# DUBEC.net
KiCad netlist of a schematic drawn in EAGLE
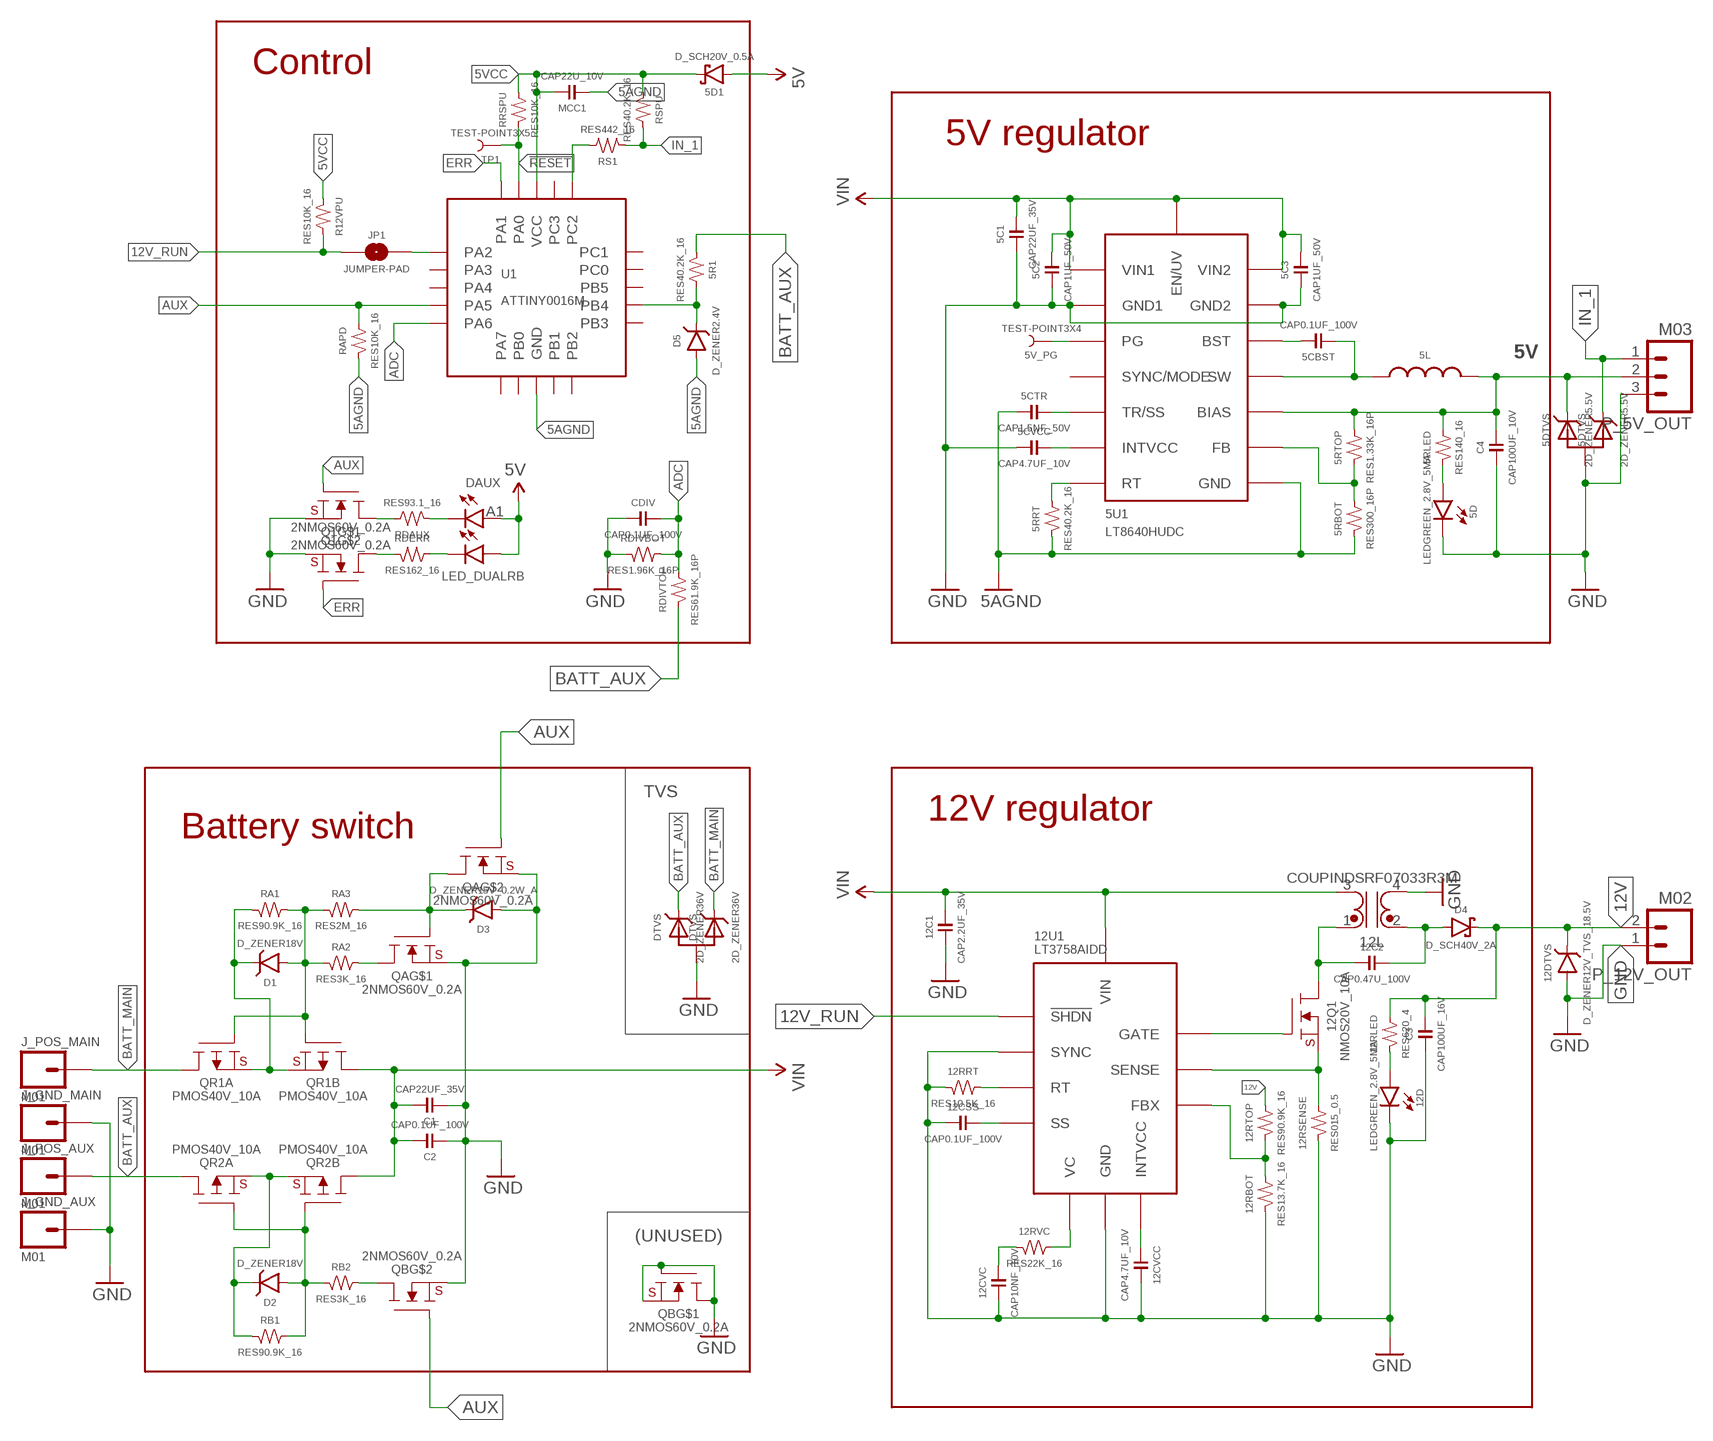
[diagram p0: schematic, sheet 1]

(export (version "E")
  (design (tool "Eeschema 10.0.6"))
  (components
    (comp (ref "5C1")
      (value "CAP22UF_35V")
      (footprint "eagle-import:0805")
      (fields
        (field (name "DIGIKEY_PART_#") "445-14428-1-ND")
        (field (name "MANUFACTURER") "TDK Corporation")
        (field (name "MFG_PART_#") "C2012X5R1V226M125AC")
      )
      (libsource (lib "eagle-import") (part "CAP22UF_35V"))
    )
    (comp (ref "5C2")
      (value "CAP1UF_50V")
      (footprint "eagle-import:0603")
      (fields
        (field (name "DIGIKEY_PART_#") "587-3247-1-ND")
        (field (name "MANUFACTURER") "Taiyo Yuden")
        (field (name "MFG_PART_#") "UMK107AB7105KA-T")
      )
      (libsource (lib "eagle-import") (part "CAP1UF_50V"))
    )
    (comp (ref "5C3")
      (value "CAP1UF_50V")
      (footprint "eagle-import:0603")
      (fields
        (field (name "DIGIKEY_PART_#") "587-3247-1-ND")
        (field (name "MANUFACTURER") "Taiyo Yuden")
        (field (name "MFG_PART_#") "UMK107AB7105KA-T")
      )
      (libsource (lib "eagle-import") (part "CAP1UF_50V"))
    )
    (comp (ref "5CBST")
      (value "CAP0.1UF_100V")
      (footprint "eagle-import:0402")
      (fields
        (field (name "DIGIKEY_PART_#") "490-10458-1-ND")
        (field (name "MANUFACTURER") "Murata Electronics North America")
        (field (name "MFG_PART_#") "GRM155R62A104KE14D")
      )
      (libsource (lib "eagle-import") (part "CAP0.1UF_100V"))
    )
    (comp (ref "5CTR")
      (value "CAP1.5NF_50V")
      (footprint "eagle-import:0402")
      (fields
        (field (name "DIGIKEY_PART_#") "490-3245-1-ND")
        (field (name "MANUFACTURER") "Murata Electronics North America")
        (field (name "MFG_PART_#") "GRM155R71H152KA01D")
      )
      (libsource (lib "eagle-import") (part "CAP1.5NF_50V"))
    )
    (comp (ref "5CVCC")
      (value "CAP4.7UF_10V")
      (footprint "eagle-import:0402")
      (fields
        (field (name "DIGIKEY_PART_#") "445-13820-1-ND")
        (field (name "MANUFACTURER") "TDK Corporation")
        (field (name "MFG_PART_#") "C1005X5R1A475K050BC")
      )
      (libsource (lib "eagle-import") (part "CAP4.7UF_10V"))
    )
    (comp (ref "5D")
      (value "LEDGREEN_2.8V_5MA")
      (footprint "eagle-import:0603+")
      (fields
        (field (name "DIGIKEY_PART_#") "160-1832-1-ND")
        (field (name "MANUFACTURER") "Lite-On Inc")
        (field (name "MFG_PART_#") "LTST-C193TGKT-5A")
      )
      (libsource (lib "eagle-import") (part "LEDGREEN_2.8V_5MA"))
    )
    (comp (ref "5D1")
      (value "D_SCH20V_0.5A")
      (footprint "eagle-import:SOD523+")
      (fields
        (field (name "DIGIKEY_PART_#") "NSR0520V2T1GOSCT-ND")
        (field (name "MANUFACTURER") "ON Semiconductor")
        (field (name "MFG_PART_#") "NSR0520V2T1G")
      )
      (libsource (lib "eagle-import") (part "D_SCH20V_0.5A"))
    )
    (comp (ref "5DTVS")
      (value "2D_ZENER5.5V")
      (footprint "eagle-import:SOT23-3")
      (fields
        (field (name "DIGIKEY_PART_#") "PACDN042Y3ROSCT-ND")
        (field (name "MANUFACTURER") "ON Semiconductor")
        (field (name "MFG_PART_#") "PACDN042Y3R")
      )
      (libsource (lib "eagle-import") (part "2D_ZENER5.5V"))
    )
    (comp (ref "5L")
      (value "I3.3UH_5A")
      (footprint "eagle-import:SRP5030")
      (fields
        (field (name "DIGIKEY_PART_#") "SRP5030TA-3R3MCT-ND")
        (field (name "MANUFACTURER") "Bourns Inc.")
        (field (name "MFG_PART_#") "SRP5030TA-3R3M")
      )
      (libsource (lib "eagle-import") (part "I3.3UH_5A"))
    )
    (comp (ref "5R1")
      (value "RES40.2K_16")
      (footprint "eagle-import:0402")
      (fields
        (field (name "DIGIKEY_PART_#") "541-40.2KLCT-ND")
        (field (name "MANUFACTURER") "Vishay Dale")
        (field (name "MFG_PART_#") "CRCW040240K2FKED")
      )
      (libsource (lib "eagle-import") (part "RES40.2K_16"))
    )
    (comp (ref "5RBOT")
      (value "RES300_16P")
      (footprint "eagle-import:0402")
      (fields
        (field (name "DIGIKEY_PART_#") "YAG1406CT-ND")
        (field (name "MANUFACTURER") "Yageo")
        (field (name "MFG_PART_#") "RT0402BRD07300RL")
      )
      (libsource (lib "eagle-import") (part "RES300_16P"))
    )
    (comp (ref "5RLED")
      (value "RES140_16")
      (footprint "eagle-import:0402")
      (fields
        (field (name "DIGIKEY_PART_#") "541-140LCT-ND")
        (field (name "MANUFACTURER") "Vishay Dale")
        (field (name "MFG_PART_#") "CRCW0402140RFKED")
      )
      (libsource (lib "eagle-import") (part "RES140_16"))
    )
    (comp (ref "5RRT")
      (value "RES40.2K_16")
      (footprint "eagle-import:0402")
      (fields
        (field (name "DIGIKEY_PART_#") "541-40.2KLCT-ND")
        (field (name "MANUFACTURER") "Vishay Dale")
        (field (name "MFG_PART_#") "CRCW040240K2FKED")
      )
      (libsource (lib "eagle-import") (part "RES40.2K_16"))
    )
    (comp (ref "5RTOP")
      (value "RES1.33K_16P")
      (footprint "eagle-import:0402")
      (fields
        (field (name "DIGIKEY_PART_#") "YAG1376CT-ND")
        (field (name "MANUFACTURER") "Yageo")
        (field (name "MFG_PART_#") "RT0402BRD071K33L")
      )
      (libsource (lib "eagle-import") (part "RES1.33K_16P"))
    )
    (comp (ref "5U1")
      (value "LT8640HUDC")
      (footprint "eagle-import:QFN-18")
      (fields
        (field (name "DIGIKEY_PART_#") "LT8640HUDC#PBF-ND")
        (field (name "MANUFACTURER") "Linear Technology")
        (field (name "MFG_PART_#") "LT8640HUDC#PBF")
      )
      (libsource (lib "eagle-import") (part "LT8640HUDC"))
    )
    (comp (ref "5V_PG")
      (value "TEST-POINT3X4")
      (footprint "eagle-import:PAD.03X.04")
      (libsource (lib "eagle-import") (part "TEST-POINT3X4"))
    )
    (comp (ref "12C1")
      (value "CAP2.2UF_35V")
      (footprint "eagle-import:0402")
      (fields
        (field (name "DIGIKEY_PART_#") "445-9028-1-ND")
        (field (name "MANUFACTURER") "TDK Corporation")
        (field (name "MFG_PART_#") "C1005X5R1V225K050BC")
      )
      (libsource (lib "eagle-import") (part "CAP2.2UF_35V"))
    )
    (comp (ref "12C2")
      (value "CAP0.47U_100V")
      (footprint "eagle-import:0805")
      (fields
        (field (name "DIGIKEY_PART_#") "490-3326-1-ND")
        (field (name "MFG_PART_#") "GRM21BR72A474KA73L")
        (field (name "TOLERANCE") "±10%")
      )
      (libsource (lib "eagle-import") (part "CAP0.47U_100V"))
    )
    (comp (ref "12CSS")
      (value "CAP0.1UF_100V")
      (footprint "eagle-import:0402")
      (fields
        (field (name "DIGIKEY_PART_#") "490-10458-1-ND")
        (field (name "MANUFACTURER") "Murata Electronics North America")
        (field (name "MFG_PART_#") "GRM155R62A104KE14D")
      )
      (libsource (lib "eagle-import") (part "CAP0.1UF_100V"))
    )
    (comp (ref "12CVC")
      (value "CAP10NF_10V")
      (footprint "eagle-import:0402")
      (fields
        (field (name "DIGIKEY_PART_#") "478-7890-1-ND")
        (field (name "MANUFACTURER") "AVX Corporation")
        (field (name "MFG_PART_#") "0402ZC103KAT2A")
      )
      (libsource (lib "eagle-import") (part "CAP10NF_10V"))
    )
    (comp (ref "12CVCC")
      (value "CAP4.7UF_10V")
      (footprint "eagle-import:0402")
      (fields
        (field (name "DIGIKEY_PART_#") "445-13820-1-ND")
        (field (name "MANUFACTURER") "TDK Corporation")
        (field (name "MFG_PART_#") "C1005X5R1A475K050BC")
      )
      (libsource (lib "eagle-import") (part "CAP4.7UF_10V"))
    )
    (comp (ref "12D")
      (value "LEDGREEN_2.8V_5MA")
      (footprint "eagle-import:0603+")
      (fields
        (field (name "DIGIKEY_PART_#") "160-1832-1-ND")
        (field (name "MANUFACTURER") "Lite-On Inc")
        (field (name "MFG_PART_#") "LTST-C193TGKT-5A")
      )
      (libsource (lib "eagle-import") (part "LEDGREEN_2.8V_5MA"))
    )
    (comp (ref "12DTVS")
      (value "D_ZENER12V_TVS_18.5V")
      (footprint "eagle-import:SOD323+")
      (fields
        (field (name "DIGIKEY_PART_#") "F6441CT-ND")
        (field (name "MANUFACTURER") "Littelfuse Inc.")
        (field (name "MFG_PART_#") "SD12-01FTG")
      )
      (libsource (lib "eagle-import") (part "D_ZENER12V_TVS_18.5V"))
    )
    (comp (ref "12L")
      (value "COUPINDSRF07033R3M")
      (footprint "eagle-import:SRF0703")
      (fields
        (field (name "DIGIKEY_PART_#") "SRF0703-3R3MCT-ND")
        (field (name "MANUFACTURER") "Bourns Inc.")
        (field (name "MFG_PART_#") "SRF0703-3R3M")
      )
      (libsource (lib "eagle-import") (part "COUPINDSRF07033R3M"))
    )
    (comp (ref "12Q1")
      (value "NMOS20V_10A")
      (footprint "eagle-import:6-PQFN")
      (fields
        (field (name "DIGIKEY_PART_#") "IRLHS6242TRPBFCT-ND")
        (field (name "MFG_PART_#") "IRLHS6242TRPBF")
        (field (name "POWER") "1.98W (Ta), 9.6W (Tc)")
      )
      (libsource (lib "eagle-import") (part "NMOS20V_10A"))
    )
    (comp (ref "12RBOT")
      (value "RES13.7K_16")
      (footprint "eagle-import:0402")
      (fields
        (field (name "DIGIKEY_PART_#") "541-13.7KLCT-ND")
        (field (name "MANUFACTURER") "Vishay Dale")
        (field (name "MFG_PART_#") "CRCW040213K7FKED")
      )
      (libsource (lib "eagle-import") (part "RES13.7K_16"))
    )
    (comp (ref "12RLED")
      (value "RES620_4")
      (footprint "eagle-import:0603")
      (fields
        (field (name "DIGIKEY_PART_#") "P620BYCT-ND")
        (field (name "MANUFACTURER") "Panasonic Electronic Components")
        (field (name "MFG_PART_#") "ERJ-PA3F6200V")
      )
      (libsource (lib "eagle-import") (part "RES620_4"))
    )
    (comp (ref "12RRT")
      (value "RES10.5K_16")
      (footprint "eagle-import:0402")
      (fields
        (field (name "DIGIKEY_PART_#") "541-10.5KLCT-ND")
        (field (name "MANUFACTURER") "Vishay Dale")
        (field (name "MFG_PART_#") "CRCW040210K5FKED")
      )
      (libsource (lib "eagle-import") (part "RES10.5K_16"))
    )
    (comp (ref "12RSENSE")
      (value "RES015_0.5")
      (footprint "eagle-import:1206")
      (fields
        (field (name "DIGIKEY_PART_#") "CSR1206FK15L0CT-ND")
        (field (name "MFG_PART_#") "CSR1206FK15L0")
        (field (name "TOLERANCE") "±1%")
      )
      (libsource (lib "eagle-import") (part "RES015_0.5"))
    )
    (comp (ref "12RTOP")
      (value "RES90.9K_16")
      (footprint "eagle-import:0402")
      (fields
        (field (name "DIGIKEY_PART_#") "541-90.9KLCT-ND")
        (field (name "MANUFACTURER") "Vishay Dale")
        (field (name "MFG_PART_#") "CRCW040290K9FKED")
      )
      (libsource (lib "eagle-import") (part "RES90.9K_16"))
    )
    (comp (ref "12RVC")
      (value "RES22K_16")
      (footprint "eagle-import:0402")
      (fields
        (field (name "DIGIKEY_PART_#") "541-22.0KLCT-ND")
        (field (name "MANUFACTURER") "Vishay Dale")
        (field (name "MFG_PART_#") "CRCW040222K0FKED")
      )
      (libsource (lib "eagle-import") (part "RES22K_16"))
    )
    (comp (ref "12U1")
      (value "LT3758AIDD")
      (footprint "eagle-import:DFN-10")
      (fields
        (field (name "DIGIKEY_PART_#") "LT3758AIDD#PBF-ND")
        (field (name "MANUFACTURER") "Linear Technology")
        (field (name "MFG_PART_#") "LT3758AIDD#PBF")
      )
      (libsource (lib "eagle-import") (part "LT3758AIDD"))
    )
    (comp (ref "C1")
      (value "CAP22UF_35V")
      (footprint "eagle-import:0805")
      (fields
        (field (name "DIGIKEY_PART_#") "445-14428-1-ND")
        (field (name "MANUFACTURER") "TDK Corporation")
        (field (name "MFG_PART_#") "C2012X5R1V226M125AC")
      )
      (libsource (lib "eagle-import") (part "CAP22UF_35V"))
    )
    (comp (ref "C2")
      (value "CAP0.1UF_100V")
      (footprint "eagle-import:0402")
      (fields
        (field (name "DIGIKEY_PART_#") "490-10458-1-ND")
        (field (name "MANUFACTURER") "Murata Electronics North America")
        (field (name "MFG_PART_#") "GRM155R62A104KE14D")
      )
      (libsource (lib "eagle-import") (part "CAP0.1UF_100V"))
    )
    (comp (ref "C3")
      (value "CAP100UF_16V")
      (footprint "eagle-import:1210")
      (fields
        (field (name "DIGIKEY_PART_#") "587-3152-1-ND")
        (field (name "MANUFACTURER") "Taiyo Yuden")
        (field (name "MFG_PART_#") "EMK325ABJ107MM-T")
      )
      (libsource (lib "eagle-import") (part "CAP100UF_16V"))
    )
    (comp (ref "C4")
      (value "CAP100UF_10V")
      (footprint "eagle-import:1210")
      (fields
        (field (name "DIGIKEY_PART_#") "587-1965-1-ND")
        (field (name "MANUFACTURER") "Taiyo Yuden")
        (field (name "MFG_PART_#") "LMK325BJ107MM-T")
      )
      (libsource (lib "eagle-import") (part "CAP100UF_10V"))
    )
    (comp (ref "CDIV")
      (value "CAP0.1UF_100V")
      (footprint "eagle-import:0402")
      (fields
        (field (name "DIGIKEY_PART_#") "490-10458-1-ND")
        (field (name "MANUFACTURER") "Murata Electronics North America")
        (field (name "MFG_PART_#") "GRM155R62A104KE14D")
      )
      (libsource (lib "eagle-import") (part "CAP0.1UF_100V"))
    )
    (comp (ref "D1")
      (value "D_ZENER18V")
      (footprint "eagle-import:SOD523+")
      (fields
        (field (name "DIGIKEY_PART_#") "DZ2S180M0LCT-ND")
        (field (name "MANUFACTURER") "Panasonic Electronic Components")
        (field (name "MFG_PART_#") "DZ2S180M0L")
      )
      (libsource (lib "eagle-import") (part "D_ZENER18V"))
    )
    (comp (ref "D2")
      (value "D_ZENER18V")
      (footprint "eagle-import:SOD523+")
      (fields
        (field (name "DIGIKEY_PART_#") "DZ2S180M0LCT-ND")
        (field (name "MANUFACTURER") "Panasonic Electronic Components")
        (field (name "MFG_PART_#") "DZ2S180M0L")
      )
      (libsource (lib "eagle-import") (part "D_ZENER18V"))
    )
    (comp (ref "D3")
      (value "D_ZENER15V_0.2W_A")
      (footprint "eagle-import:SOD523+")
      (fields
        (field (name "DIGIKEY_PART_#") "MM5Z15VT1GOSCT-ND")
        (field (name "MANUFACTURER") "ON Semiconductor")
        (field (name "MFG_PART_#") "MM5Z15VT1G")
      )
      (libsource (lib "eagle-import") (part "D_ZENER15V_0.2W_A"))
    )
    (comp (ref "D4")
      (value "D_SCH40V_2A")
      (footprint "eagle-import:DO-214AC")
      (fields (field (name "DIGIKEY_PART_#") "641-1698-1-ND") (field (name "MFG_PART_#") "CDBA240LL-HF"))
      (libsource (lib "eagle-import") (part "D_SCH40V_2A"))
    )
    (comp (ref "D5")
      (value "D_ZENER2.4V")
      (footprint "eagle-import:SOD523+")
      (fields
        (field (name "DIGIKEY_PART_#") "BZT585B2V4T-7DICT-ND")
        (field (name "MANUFACTURER") "Diodes Incorporated")
        (field (name "MFG_PART_#") "BZT585B2V4T-7")
      )
      (libsource (lib "eagle-import") (part "D_ZENER2.4V"))
    )
    (comp (ref "DAUX")
      (value "LED_DUALRB")
      (footprint "eagle-import:0603+DUAL")
      (fields
        (field (name "DIGIKEY_PART_#") "754-1853-1-ND")
        (field (name "MANUFACTURER") "Kingbright")
        (field (name "MFG_PART_#") "APHB1608QBDSURKC")
      )
      (libsource (lib "eagle-import") (part "LED_DUALRB"))
    )
    (comp (ref "DTVS")
      (value "2D_ZENER36V")
      (footprint "eagle-import:SOT23-3")
      (fields
        (field (name "DIGIKEY_PART_#") "F6350CT-ND")
        (field (name "MANUFACTURER") "Littelfuse Inc.")
        (field (name "MFG_PART_#") "SM36-02HTG")
      )
      (libsource (lib "eagle-import") (part "2D_ZENER36V"))
    )
    (comp (ref "JP1")
      (value "JUMPER-PAD")
      (footprint "eagle-import:JUMPER-PAD-ROUND")
      (libsource (lib "eagle-import") (part "JUMPER-PAD"))
    )
    (comp (ref "J_GND_AUX")
      (value "M01")
      (footprint "eagle-import:1X01_NO_SILK")
      (libsource (lib "eagle-import") (part "M01"))
    )
    (comp (ref "J_GND_MAIN")
      (value "M01")
      (footprint "eagle-import:1X01_NO_SILK")
      (libsource (lib "eagle-import") (part "M01"))
    )
    (comp (ref "J_POS_AUX")
      (value "M01")
      (footprint "eagle-import:1X01_NO_SILK")
      (libsource (lib "eagle-import") (part "M01"))
    )
    (comp (ref "J_POS_MAIN")
      (value "M01")
      (footprint "eagle-import:1X01_NO_SILK")
      (libsource (lib "eagle-import") (part "M01"))
    )
    (comp (ref "MCC1")
      (value "CAP22U_10V")
      (footprint "eagle-import:0603")
      (fields
        (field (name "DIGIKEY_PART_#") "1276-6504-1-ND")
        (field (name "MANUFACTURER") "Samsung Electro-Mechanics America, Inc.")
        (field (name "MFG_PART_#") "CL10A226MPCNUBE")
      )
      (libsource (lib "eagle-import") (part "CAP22U_10V"))
    )
    (comp (ref "P_5V_OUT")
      (value "M03")
      (footprint "eagle-import:1X03_NO_SILK")
      (libsource (lib "eagle-import") (part "M03"))
    )
    (comp (ref "P_12V_OUT")
      (value "M02")
      (footprint "eagle-import:1X02_NO_SILK")
      (libsource (lib "eagle-import") (part "M02"))
    )
    (comp (ref "Q1")
      (value "2NMOS60V_0.2A")
      (footprint "eagle-import:SOT-666")
      (fields
        (field (name "DIGIKEY_PART_#") "SSM6N7002BFELMCT-ND")
        (field (name "MANUFACTURER") "Toshiba Semiconductor and Storage")
        (field (name "MFG_PART_#") "SSM6N7002BFE,LM")
      )
      (libsource (lib "eagle-import") (part "2NMOS60V_0.2A"))
    )
    (comp (ref "QA")
      (value "2NMOS60V_0.2A")
      (footprint "eagle-import:SOT-666")
      (fields
        (field (name "DIGIKEY_PART_#") "SSM6N7002BFELMCT-ND")
        (field (name "MANUFACTURER") "Toshiba Semiconductor and Storage")
        (field (name "MFG_PART_#") "SSM6N7002BFE,LM")
      )
      (libsource (lib "eagle-import") (part "2NMOS60V_0.2A"))
    )
    (comp (ref "QB")
      (value "2NMOS60V_0.2A")
      (footprint "eagle-import:SOT-666")
      (fields
        (field (name "DIGIKEY_PART_#") "SSM6N7002BFELMCT-ND")
        (field (name "MANUFACTURER") "Toshiba Semiconductor and Storage")
        (field (name "MFG_PART_#") "SSM6N7002BFE,LM")
      )
      (libsource (lib "eagle-import") (part "2NMOS60V_0.2A"))
    )
    (comp (ref "QR1A")
      (value "PMOS40V_10A")
      (footprint "eagle-import:POWERDI3333-8")
      (fields
        (field (name "MANUFACTURER") "Diodes Incorporated")
        (field (name "MFG_PART_#") "DMP4013LFG-7")
        (field (name "MOUSER_PART_#") "621-DMP4013LFG-7")
      )
      (libsource (lib "eagle-import") (part "PMOS40V_10A"))
    )
    (comp (ref "QR1B")
      (value "PMOS40V_10A")
      (footprint "eagle-import:POWERDI3333-8")
      (fields
        (field (name "MANUFACTURER") "Diodes Incorporated")
        (field (name "MFG_PART_#") "DMP4013LFG-7")
        (field (name "MOUSER_PART_#") "621-DMP4013LFG-7")
      )
      (libsource (lib "eagle-import") (part "PMOS40V_10A"))
    )
    (comp (ref "QR2A")
      (value "PMOS40V_10A")
      (footprint "eagle-import:POWERDI3333-8")
      (fields
        (field (name "MANUFACTURER") "Diodes Incorporated")
        (field (name "MFG_PART_#") "DMP4013LFG-7")
        (field (name "MOUSER_PART_#") "621-DMP4013LFG-7")
      )
      (libsource (lib "eagle-import") (part "PMOS40V_10A"))
    )
    (comp (ref "QR2B")
      (value "PMOS40V_10A")
      (footprint "eagle-import:POWERDI3333-8")
      (fields
        (field (name "MANUFACTURER") "Diodes Incorporated")
        (field (name "MFG_PART_#") "DMP4013LFG-7")
        (field (name "MOUSER_PART_#") "621-DMP4013LFG-7")
      )
      (libsource (lib "eagle-import") (part "PMOS40V_10A"))
    )
    (comp (ref "R12VPU")
      (value "RES10K_16")
      (footprint "eagle-import:0402")
      (fields
        (field (name "DIGIKEY_PART_#") "541-10.0KLCT-ND")
        (field (name "MANUFACTURER") "Vishay Dale")
        (field (name "MFG_PART_#") "CRCW040210K0FKED")
      )
      (libsource (lib "eagle-import") (part "RES10K_16"))
    )
    (comp (ref "RA1")
      (value "RES90.9K_16")
      (footprint "eagle-import:0402")
      (fields
        (field (name "DIGIKEY_PART_#") "541-90.9KLCT-ND")
        (field (name "MANUFACTURER") "Vishay Dale")
        (field (name "MFG_PART_#") "CRCW040290K9FKED")
      )
      (libsource (lib "eagle-import") (part "RES90.9K_16"))
    )
    (comp (ref "RA2")
      (value "RES3K_16")
      (footprint "eagle-import:0402")
      (fields
        (field (name "DIGIKEY_PART_#") "541-3.00KLCT-ND")
        (field (name "MANUFACTURER") "Vishay Dale")
        (field (name "MFG_PART_#") "CRCW04023K00FKED")
      )
      (libsource (lib "eagle-import") (part "RES3K_16"))
    )
    (comp (ref "RA3")
      (value "RES2M_16")
      (footprint "eagle-import:0402")
      (fields
        (field (name "DIGIKEY_PART_#") "541-2.00MLCT-ND")
        (field (name "MANUFACTURER") "Vishay Dale")
        (field (name "MFG_PART_#") "CRCW04022M00FKED")
      )
      (libsource (lib "eagle-import") (part "RES2M_16"))
    )
    (comp (ref "RAPD")
      (value "RES10K_16")
      (footprint "eagle-import:0402")
      (fields
        (field (name "DIGIKEY_PART_#") "541-10.0KLCT-ND")
        (field (name "MANUFACTURER") "Vishay Dale")
        (field (name "MFG_PART_#") "CRCW040210K0FKED")
      )
      (libsource (lib "eagle-import") (part "RES10K_16"))
    )
    (comp (ref "RB1")
      (value "RES90.9K_16")
      (footprint "eagle-import:0402")
      (fields
        (field (name "DIGIKEY_PART_#") "541-90.9KLCT-ND")
        (field (name "MANUFACTURER") "Vishay Dale")
        (field (name "MFG_PART_#") "CRCW040290K9FKED")
      )
      (libsource (lib "eagle-import") (part "RES90.9K_16"))
    )
    (comp (ref "RB2")
      (value "RES3K_16")
      (footprint "eagle-import:0402")
      (fields
        (field (name "DIGIKEY_PART_#") "541-3.00KLCT-ND")
        (field (name "MANUFACTURER") "Vishay Dale")
        (field (name "MFG_PART_#") "CRCW04023K00FKED")
      )
      (libsource (lib "eagle-import") (part "RES3K_16"))
    )
    (comp (ref "RDAUX")
      (value "RES93.1_16")
      (footprint "eagle-import:0402")
      (fields
        (field (name "DIGIKEY_PART_#") "541-93.1LCT-ND")
        (field (name "MANUFACTURER") "Vishay Dale")
        (field (name "MFG_PART_#") "CRCW040293R1FKED")
      )
      (libsource (lib "eagle-import") (part "RES93.1_16"))
    )
    (comp (ref "RDERR")
      (value "RES162_16")
      (footprint "eagle-import:0402")
      (fields
        (field (name "DIGIKEY_PART_#") "541-162LCT-ND")
        (field (name "MANUFACTURER") "Vishay Dale")
        (field (name "MFG_PART_#") "CRCW0402162RFKED")
      )
      (libsource (lib "eagle-import") (part "RES162_16"))
    )
    (comp (ref "RDIVBOT")
      (value "RES1.96K_16P")
      (footprint "eagle-import:0402")
      (fields
        (field (name "DIGIKEY_PART_#") "YAG1385CT-ND")
        (field (name "MANUFACTURER") "Yageo")
        (field (name "MFG_PART_#") "RT0402BRD071K96L")
      )
      (libsource (lib "eagle-import") (part "RES1.96K_16P"))
    )
    (comp (ref "RDIVTOP")
      (value "RES61.9K_16P")
      (footprint "eagle-import:0402")
      (fields
        (field (name "DIGIKEY_PART_#") "YAG1462CT-ND")
        (field (name "MANUFACTURER") "Yageo")
        (field (name "MFG_PART_#") "RT0402BRD0761K9L")
      )
      (libsource (lib "eagle-import") (part "RES61.9K_16P"))
    )
    (comp (ref "RRSPU")
      (value "RES10K_16")
      (footprint "eagle-import:0402")
      (fields
        (field (name "DIGIKEY_PART_#") "541-10.0KLCT-ND")
        (field (name "MANUFACTURER") "Vishay Dale")
        (field (name "MFG_PART_#") "CRCW040210K0FKED")
      )
      (libsource (lib "eagle-import") (part "RES10K_16"))
    )
    (comp (ref "RS1")
      (value "RES442_16")
      (footprint "eagle-import:0402")
      (fields
        (field (name "DIGIKEY_PART_#") "541-442LCT-ND")
        (field (name "MANUFACTURER") "Vishay Dale")
        (field (name "MFG_PART_#") "CRCW0402442RFKED")
      )
      (libsource (lib "eagle-import") (part "RES442_16"))
    )
    (comp (ref "RSPU")
      (value "RES40.2K_16")
      (footprint "eagle-import:0402")
      (fields
        (field (name "DIGIKEY_PART_#") "541-40.2KLCT-ND")
        (field (name "MANUFACTURER") "Vishay Dale")
        (field (name "MFG_PART_#") "CRCW040240K2FKED")
      )
      (libsource (lib "eagle-import") (part "RES40.2K_16"))
    )
    (comp (ref "TP1")
      (value "TEST-POINT3X5")
      (footprint "eagle-import:PAD.03X.05")
      (libsource (lib "eagle-import") (part "TEST-POINT3X5"))
    )
    (comp (ref "U1")
      (value "ATTINY0016M")
      (footprint "eagle-import:20-VQFN-2")
      (fields
        (field (name "DIGIKEY_PART_#") "ATTINY1616-MFRCT-ND")
        (field (name "MANUFACTURER") "Microchip Technology")
        (field (name "MFG_PART_#") "ATTINY1616-MFR")
      )
      (libsource (lib "eagle-import") (part "ATTINY0016M"))
    )
  )
  (nets
    (net (code "1") (name "/~{RESET}") (class "Default")
      (node (ref "RRSPU") (pin "1") (pinfunction "1_1") (pintype "passive"))
      (node (ref "TP1") (pin "P$1") (pinfunction "1_P$1") (pintype "bidirectional"))
      (node (ref "U1") (pin "19") (pinfunction "PA0_19") (pintype "passive"))
    )
    (net (code "2") (name "5AGND") (class "Default")
      (node (ref "5CTR") (pin "1") (pinfunction "1_1") (pintype "passive"))
      (node (ref "5RBOT") (pin "1") (pinfunction "1_1") (pintype "passive"))
      (node (ref "5RRT") (pin "1") (pinfunction "1_1") (pintype "passive"))
      (node (ref "5U1") (pin "18") (pinfunction "GND_18") (pintype "passive"))
      (node (ref "D5") (pin "A") (pinfunction "A_A") (pintype "passive"))
      (node (ref "MCC1") (pin "1") (pinfunction "1_1") (pintype "passive"))
      (node (ref "RAPD") (pin "1") (pinfunction "1_1") (pintype "passive"))
      (node (ref "U1") (pin "3") (pinfunction "GND_3") (pintype "passive"))
      (node (ref "U1") (pin "PAD") (pinfunction "GND_PAD") (pintype "passive"))
    )
    (net (code "3") (name "5V") (class "Default")
      (node (ref "5D1") (pin "A") (pinfunction "A_A") (pintype "passive"))
      (node (ref "5DTVS") (pin "1") (pinfunction "C1_1") (pintype "passive"))
      (node (ref "5L") (pin "2") (pinfunction "2_2") (pintype "passive"))
      (node (ref "5RLED") (pin "2") (pinfunction "2_2") (pintype "passive"))
      (node (ref "5RTOP") (pin "2") (pinfunction "2_2") (pintype "passive"))
      (node (ref "5U1") (pin "1") (pinfunction "BIAS_1") (pintype "passive"))
      (node (ref "C4") (pin "2") (pinfunction "2_2") (pintype "passive"))
      (node (ref "DAUX") (pin "A1") (pinfunction "A1_A1") (pintype "passive"))
      (node (ref "DAUX") (pin "A2") (pinfunction "A2_A2") (pintype "passive"))
      (node (ref "P_5V_OUT") (pin "2") (pinfunction "2_2") (pintype "passive"))
    )
    (net (code "4") (name "5VCC") (class "Default")
      (node (ref "5D1") (pin "C") (pinfunction "C_C") (pintype "passive"))
      (node (ref "MCC1") (pin "2") (pinfunction "2_2") (pintype "passive"))
      (node (ref "R12VPU") (pin "1") (pinfunction "1_1") (pintype "passive"))
      (node (ref "RRSPU") (pin "2") (pinfunction "2_2") (pintype "passive"))
      (node (ref "RSPU") (pin "1") (pinfunction "1_1") (pintype "passive"))
      (node (ref "U1") (pin "4") (pinfunction "VCC_4") (pintype "passive"))
    )
    (net (code "5") (name "12V") (class "Default")
      (node (ref "12DTVS") (pin "C") (pinfunction "C_C") (pintype "passive"))
      (node (ref "12RLED") (pin "2") (pinfunction "2_2") (pintype "passive"))
      (node (ref "12RTOP") (pin "2") (pinfunction "2_2") (pintype "passive"))
      (node (ref "C3") (pin "2") (pinfunction "2_2") (pintype "passive"))
      (node (ref "D4") (pin "C") (pinfunction "C_C") (pintype "passive"))
      (node (ref "P_12V_OUT") (pin "2") (pinfunction "2_2") (pintype "passive"))
    )
    (net (code "6") (name "12V_RUN") (class "Default")
      (node (ref "12U1") (pin "9") (pinfunction "~{SHDN}_9") (pintype "input"))
      (node (ref "JP1") (pin "1") (pinfunction "1_1") (pintype "passive"))
      (node (ref "R12VPU") (pin "2") (pinfunction "2_2") (pintype "passive"))
    )
    (net (code "7") (name "ADC") (class "Default")
      (node (ref "CDIV") (pin "2") (pinfunction "2_2") (pintype "passive"))
      (node (ref "RDIVBOT") (pin "2") (pinfunction "2_2") (pintype "passive"))
      (node (ref "RDIVTOP") (pin "2") (pinfunction "2_2") (pintype "passive"))
      (node (ref "U1") (pin "7") (pinfunction "PA6_7") (pintype "passive"))
    )
    (net (code "8") (name "AUX") (class "Default")
      (node (ref "Q1") (pin "2") (pinfunction "G_2") (pintype "passive"))
      (node (ref "QA") (pin "5") (pinfunction "G_5") (pintype "passive"))
      (node (ref "QB") (pin "5") (pinfunction "G_5") (pintype "passive"))
      (node (ref "RAPD") (pin "2") (pinfunction "2_2") (pintype "passive"))
      (node (ref "U1") (pin "6") (pinfunction "PA5_6") (pintype "passive"))
    )
    (net (code "9") (name "BATT_AUX") (class "Default")
      (node (ref "5R1") (pin "1") (pinfunction "1_1") (pintype "passive"))
      (node (ref "DTVS") (pin "1") (pinfunction "C1_1") (pintype "passive"))
      (node (ref "J_POS_AUX") (pin "1") (pinfunction "1_1") (pintype "passive"))
      (node (ref "QR2A") (pin "D") (pinfunction "D_D") (pintype "passive"))
      (node (ref "RDIVTOP") (pin "1") (pinfunction "1_1") (pintype "passive"))
    )
    (net (code "10") (name "BATT_MAIN") (class "Default")
      (node (ref "DTVS") (pin "2") (pinfunction "C2_2") (pintype "passive"))
      (node (ref "J_POS_MAIN") (pin "1") (pinfunction "1_1") (pintype "passive"))
      (node (ref "QR1A") (pin "D") (pinfunction "D_D") (pintype "passive"))
    )
    (net (code "11") (name "ERR") (class "Default")
      (node (ref "Q1") (pin "5") (pinfunction "G_5") (pintype "passive"))
      (node (ref "U1") (pin "20") (pinfunction "PA1_20") (pintype "passive"))
    )
    (net (code "12") (name "GND") (class "Default")
      (node (ref "12C1") (pin "1") (pinfunction "1_1") (pintype "passive"))
      (node (ref "12CSS") (pin "1") (pinfunction "1_1") (pintype "passive"))
      (node (ref "12CVC") (pin "1") (pinfunction "1_1") (pintype "passive"))
      (node (ref "12CVCC") (pin "2") (pinfunction "2_2") (pintype "passive"))
      (node (ref "12D") (pin "C") (pinfunction "C_C") (pintype "passive"))
      (node (ref "12DTVS") (pin "A") (pinfunction "A_A") (pintype "passive"))
      (node (ref "12L") (pin "4") (pinfunction "B2_4") (pintype "passive"))
      (node (ref "12RBOT") (pin "1") (pinfunction "1_1") (pintype "passive"))
      (node (ref "12RRT") (pin "1") (pinfunction "1_1") (pintype "passive"))
      (node (ref "12RSENSE") (pin "1") (pinfunction "1_1") (pintype "passive"))
      (node (ref "12U1") (pin "5") (pinfunction "SYNC_5") (pintype "input"))
      (node (ref "12U1") (pin "PAD") (pinfunction "GND_PAD") (pintype "passive"))
      (node (ref "5C1") (pin "1") (pinfunction "1_1") (pintype "passive"))
      (node (ref "5C2") (pin "1") (pinfunction "1_1") (pintype "passive"))
      (node (ref "5C3") (pin "1") (pinfunction "1_1") (pintype "passive"))
      (node (ref "5CVCC") (pin "1") (pinfunction "1_1") (pintype "passive"))
      (node (ref "5D") (pin "C") (pinfunction "C_C") (pintype "passive"))
      (node (ref "5DTVS") (pin "3") (pinfunction "A_3") (pintype "passive"))
      (node (ref "5U1") (pin "10") (pinfunction "GND2_10") (pintype "passive"))
      (node (ref "5U1") (pin "11") (pinfunction "GND2_11") (pintype "passive"))
      (node (ref "5U1") (pin "6") (pinfunction "GND1_6") (pintype "passive"))
      (node (ref "5U1") (pin "7") (pinfunction "GND1_7") (pintype "passive"))
      (node (ref "C1") (pin "1") (pinfunction "1_1") (pintype "passive"))
      (node (ref "C2") (pin "1") (pinfunction "1_1") (pintype "passive"))
      (node (ref "C3") (pin "1") (pinfunction "1_1") (pintype "passive"))
      (node (ref "C4") (pin "1") (pinfunction "1_1") (pintype "passive"))
      (node (ref "CDIV") (pin "1") (pinfunction "1_1") (pintype "passive"))
      (node (ref "D3") (pin "A") (pinfunction "A_A") (pintype "passive"))
      (node (ref "DTVS") (pin "3") (pinfunction "A_3") (pintype "passive"))
      (node (ref "J_GND_AUX") (pin "1") (pinfunction "1_1") (pintype "passive"))
      (node (ref "J_GND_MAIN") (pin "1") (pinfunction "1_1") (pintype "passive"))
      (node (ref "P_12V_OUT") (pin "1") (pinfunction "1_1") (pintype "passive"))
      (node (ref "P_5V_OUT") (pin "3") (pinfunction "3_3") (pintype "passive"))
      (node (ref "Q1") (pin "1") (pinfunction "S_1") (pintype "passive"))
      (node (ref "Q1") (pin "4") (pinfunction "S_4") (pintype "passive"))
      (node (ref "QA") (pin "1") (pinfunction "S_1") (pintype "passive"))
      (node (ref "QA") (pin "4") (pinfunction "S_4") (pintype "passive"))
      (node (ref "QB") (pin "1") (pinfunction "S_1") (pintype "passive"))
      (node (ref "QB") (pin "2") (pinfunction "G_2") (pintype "passive"))
      (node (ref "QB") (pin "4") (pinfunction "S_4") (pintype "passive"))
      (node (ref "QB") (pin "6") (pinfunction "D_6") (pintype "passive"))
      (node (ref "RDIVBOT") (pin "1") (pinfunction "1_1") (pintype "passive"))
    )
    (net (code "13") (name "IN_1") (class "Default")
      (node (ref "5DTVS") (pin "2") (pinfunction "C2_2") (pintype "passive"))
      (node (ref "P_5V_OUT") (pin "1") (pinfunction "1_1") (pintype "passive"))
      (node (ref "RS1") (pin "1") (pinfunction "1_1") (pintype "passive"))
      (node (ref "RSPU") (pin "2") (pinfunction "2_2") (pintype "passive"))
    )
    (net (code "14") (name "Net-(5CBST-Pad1)") (class "Default")
      (node (ref "5CBST") (pin "1") (pinfunction "1_1") (pintype "passive"))
      (node (ref "5L") (pin "1") (pinfunction "1_1") (pintype "passive"))
      (node (ref "5U1") (pin "21") (pinfunction "SW_21") (pintype "passive"))
      (node (ref "5U1") (pin "22") (pinfunction "SW_22") (pintype "passive"))
      (node (ref "5U1") (pin "8-9") (pinfunction "SW_8-9") (pintype "passive"))
    )
    (net (code "15") (name "Net-(5D-PadA)") (class "Default")
      (node (ref "5D") (pin "A") (pinfunction "A_A") (pintype "passive"))
      (node (ref "5RLED") (pin "1") (pinfunction "1_1") (pintype "passive"))
    )
    (net (code "16") (name "Net-(5U1-BST)") (class "Default")
      (node (ref "5CBST") (pin "2") (pinfunction "2_2") (pintype "passive"))
      (node (ref "5U1") (pin "3") (pinfunction "BST_3") (pintype "passive"))
    )
    (net (code "17") (name "Net-(5U1-FB)") (class "Default")
      (node (ref "5RBOT") (pin "2") (pinfunction "2_2") (pintype "passive"))
      (node (ref "5RTOP") (pin "1") (pinfunction "1_1") (pintype "passive"))
      (node (ref "5U1") (pin "20") (pinfunction "FB_20") (pintype "passive"))
    )
    (net (code "18") (name "Net-(5U1-INTVCC)") (class "Default")
      (node (ref "5CVCC") (pin "2") (pinfunction "2_2") (pintype "passive"))
      (node (ref "5U1") (pin "2") (pinfunction "INTVCC_2") (pintype "passive"))
    )
    (net (code "19") (name "Net-(5U1-PG)") (class "Default")
      (node (ref "5U1") (pin "19") (pinfunction "PG_19") (pintype "passive"))
      (node (ref "5V_PG") (pin "P$1") (pinfunction "1_P$1") (pintype "bidirectional"))
    )
    (net (code "20") (name "Net-(5U1-RT)") (class "Default")
      (node (ref "5RRT") (pin "2") (pinfunction "2_2") (pintype "passive"))
      (node (ref "5U1") (pin "15") (pinfunction "RT_15") (pintype "passive"))
    )
    (net (code "21") (name "Net-(5U1-TR{slash}SS)") (class "Default")
      (node (ref "5CTR") (pin "2") (pinfunction "2_2") (pintype "passive"))
      (node (ref "5U1") (pin "16") (pinfunction "TR/SS_16") (pintype "passive"))
    )
    (net (code "22") (name "Net-(12CVC-Pad2)") (class "Default")
      (node (ref "12CVC") (pin "2") (pinfunction "2_2") (pintype "passive"))
      (node (ref "12RVC") (pin "1") (pinfunction "1_1") (pintype "passive"))
    )
    (net (code "23") (name "Net-(12D-PadA)") (class "Default")
      (node (ref "12D") (pin "A") (pinfunction "A_A") (pintype "passive"))
      (node (ref "12RLED") (pin "1") (pinfunction "1_1") (pintype "passive"))
    )
    (net (code "24") (name "Net-(12L-A1)") (class "Default")
      (node (ref "12C2") (pin "1") (pinfunction "1_1") (pintype "passive"))
      (node (ref "12L") (pin "1") (pinfunction "A1_1") (pintype "passive"))
      (node (ref "12Q1") (pin "D") (pinfunction "D_D") (pintype "passive"))
    )
    (net (code "25") (name "Net-(12L-B1)") (class "Default")
      (node (ref "12C2") (pin "2") (pinfunction "2_2") (pintype "passive"))
      (node (ref "12L") (pin "2") (pinfunction "B1_2") (pintype "passive"))
      (node (ref "D4") (pin "A") (pinfunction "A_A") (pintype "passive"))
    )
    (net (code "26") (name "Net-(12U1-FBX)") (class "Default")
      (node (ref "12RBOT") (pin "2") (pinfunction "2_2") (pintype "passive"))
      (node (ref "12RTOP") (pin "1") (pinfunction "1_1") (pintype "passive"))
      (node (ref "12U1") (pin "2") (pinfunction "FBX_2") (pintype "input"))
    )
    (net (code "27") (name "Net-(12U1-GATE)") (class "Default")
      (node (ref "12Q1") (pin "G") (pinfunction "G_G") (pintype "passive"))
      (node (ref "12U1") (pin "7") (pinfunction "GATE_7") (pintype "passive"))
    )
    (net (code "28") (name "Net-(12U1-INTVCC)") (class "Default")
      (node (ref "12CVCC") (pin "1") (pinfunction "1_1") (pintype "passive"))
      (node (ref "12U1") (pin "8") (pinfunction "INTVCC_8") (pintype "passive"))
    )
    (net (code "29") (name "Net-(12U1-RT)") (class "Default")
      (node (ref "12RRT") (pin "2") (pinfunction "2_2") (pintype "passive"))
      (node (ref "12U1") (pin "4") (pinfunction "RT_4") (pintype "input"))
    )
    (net (code "30") (name "Net-(12U1-SENSE)") (class "Default")
      (node (ref "12Q1") (pin "S") (pinfunction "S_S") (pintype "passive"))
      (node (ref "12RSENSE") (pin "2") (pinfunction "2_2") (pintype "passive"))
      (node (ref "12U1") (pin "6") (pinfunction "SENSE_6") (pintype "passive"))
    )
    (net (code "31") (name "Net-(12U1-SS)") (class "Default")
      (node (ref "12CSS") (pin "2") (pinfunction "2_2") (pintype "passive"))
      (node (ref "12U1") (pin "3") (pinfunction "SS_3") (pintype "passive"))
    )
    (net (code "32") (name "Net-(12U1-VC)") (class "Default")
      (node (ref "12RVC") (pin "2") (pinfunction "2_2") (pintype "passive"))
      (node (ref "12U1") (pin "1") (pinfunction "VC_1") (pintype "passive"))
    )
    (net (code "33") (name "Net-(D1-PadA)") (class "Default")
      (node (ref "D1") (pin "A") (pinfunction "A_A") (pintype "passive"))
      (node (ref "QR1A") (pin "G") (pinfunction "G_G") (pintype "passive"))
      (node (ref "QR1B") (pin "G") (pinfunction "G_G") (pintype "passive"))
      (node (ref "RA1") (pin "2") (pinfunction "2_2") (pintype "passive"))
      (node (ref "RA2") (pin "1") (pinfunction "1_1") (pintype "passive"))
      (node (ref "RA3") (pin "1") (pinfunction "1_1") (pintype "passive"))
    )
    (net (code "34") (name "Net-(D1-PadC)") (class "Default")
      (node (ref "D1") (pin "C") (pinfunction "C_C") (pintype "passive"))
      (node (ref "QR1A") (pin "S") (pinfunction "S_S") (pintype "passive"))
      (node (ref "QR1B") (pin "S") (pinfunction "S_S") (pintype "passive"))
      (node (ref "RA1") (pin "1") (pinfunction "1_1") (pintype "passive"))
    )
    (net (code "35") (name "Net-(D2-PadA)") (class "Default")
      (node (ref "D2") (pin "A") (pinfunction "A_A") (pintype "passive"))
      (node (ref "QR2A") (pin "G") (pinfunction "G_G") (pintype "passive"))
      (node (ref "QR2B") (pin "G") (pinfunction "G_G") (pintype "passive"))
      (node (ref "RB1") (pin "2") (pinfunction "2_2") (pintype "passive"))
      (node (ref "RB2") (pin "1") (pinfunction "1_1") (pintype "passive"))
    )
    (net (code "36") (name "Net-(D2-PadC)") (class "Default")
      (node (ref "D2") (pin "C") (pinfunction "C_C") (pintype "passive"))
      (node (ref "QR2A") (pin "S") (pinfunction "S_S") (pintype "passive"))
      (node (ref "QR2B") (pin "S") (pinfunction "S_S") (pintype "passive"))
      (node (ref "RB1") (pin "1") (pinfunction "1_1") (pintype "passive"))
    )
    (net (code "37") (name "Net-(DAUX-PadC1)") (class "Default")
      (node (ref "DAUX") (pin "C1") (pinfunction "C1_C1") (pintype "passive"))
      (node (ref "RDAUX") (pin "2") (pinfunction "2_2") (pintype "passive"))
    )
    (net (code "38") (name "Net-(DAUX-PadC2)") (class "Default")
      (node (ref "DAUX") (pin "C2") (pinfunction "C2_C2") (pintype "passive"))
      (node (ref "RDERR") (pin "1") (pinfunction "1_1") (pintype "passive"))
    )
    (net (code "39") (name "Net-(Q1A-D)") (class "Default")
      (node (ref "Q1") (pin "6") (pinfunction "D_6") (pintype "passive"))
      (node (ref "RDAUX") (pin "1") (pinfunction "1_1") (pintype "passive"))
    )
    (net (code "40") (name "Net-(Q1B-D)") (class "Default")
      (node (ref "Q1") (pin "3") (pinfunction "D_3") (pintype "passive"))
      (node (ref "RDERR") (pin "2") (pinfunction "2_2") (pintype "passive"))
    )
    (net (code "41") (name "Net-(QAA-D)") (class "Default")
      (node (ref "QA") (pin "6") (pinfunction "D_6") (pintype "passive"))
      (node (ref "RA2") (pin "2") (pinfunction "2_2") (pintype "passive"))
    )
    (net (code "42") (name "Net-(QAA-G)") (class "Default")
      (node (ref "D3") (pin "C") (pinfunction "C_C") (pintype "passive"))
      (node (ref "QA") (pin "2") (pinfunction "G_2") (pintype "passive"))
      (node (ref "QA") (pin "3") (pinfunction "D_3") (pintype "passive"))
      (node (ref "RA3") (pin "2") (pinfunction "2_2") (pintype "passive"))
    )
    (net (code "43") (name "Net-(QBB-D)") (class "Default")
      (node (ref "QB") (pin "3") (pinfunction "D_3") (pintype "passive"))
      (node (ref "RB2") (pin "2") (pinfunction "2_2") (pintype "passive"))
    )
    (net (code "44") (name "Net-(U1-PA2)") (class "Default")
      (node (ref "JP1") (pin "2") (pinfunction "2_2") (pintype "passive"))
      (node (ref "U1") (pin "1") (pinfunction "PA2_1") (pintype "passive"))
    )
    (net (code "45") (name "Net-(U1-PB4)") (class "Default")
      (node (ref "5R1") (pin "2") (pinfunction "2_2") (pintype "passive"))
      (node (ref "D5") (pin "C") (pinfunction "C_C") (pintype "passive"))
      (node (ref "U1") (pin "10") (pinfunction "PB4_10") (pintype "passive"))
    )
    (net (code "46") (name "Net-(U1-PC2)") (class "Default")
      (node (ref "RS1") (pin "2") (pinfunction "2_2") (pintype "passive"))
      (node (ref "U1") (pin "17") (pinfunction "PC2_17") (pintype "passive"))
    )
    (net (code "47") (name "VIN") (class "Default")
      (node (ref "12C1") (pin "2") (pinfunction "2_2") (pintype "passive"))
      (node (ref "12L") (pin "3") (pinfunction "A2_3") (pintype "passive"))
      (node (ref "12U1") (pin "10") (pinfunction "VIN_10") (pintype "passive"))
      (node (ref "5C1") (pin "2") (pinfunction "2_2") (pintype "passive"))
      (node (ref "5C2") (pin "2") (pinfunction "2_2") (pintype "passive"))
      (node (ref "5C3") (pin "2") (pinfunction "2_2") (pintype "passive"))
      (node (ref "5U1") (pin "13") (pinfunction "VIN2_13") (pintype "passive"))
      (node (ref "5U1") (pin "14") (pinfunction "EN/UV_14") (pintype "passive"))
      (node (ref "5U1") (pin "4") (pinfunction "VIN1_4") (pintype "passive"))
      (node (ref "C1") (pin "2") (pinfunction "2_2") (pintype "passive"))
      (node (ref "C2") (pin "2") (pinfunction "2_2") (pintype "passive"))
      (node (ref "QR1B") (pin "D") (pinfunction "D_D") (pintype "passive"))
      (node (ref "QR2B") (pin "D") (pinfunction "D_D") (pintype "passive"))
    )
    (net (code "48") (name "unconnected-(5U1-SYNC{slash}MODE-Pad17)") (class "Default")
      (node (ref "5U1") (pin "17") (pinfunction "SYNC/MODE_17") (pintype "passive"))
    )
    (net (code "49") (name "unconnected-(U1-PA3-Pad2)") (class "Default")
      (node (ref "U1") (pin "2") (pinfunction "PA3_2") (pintype "passive"))
    )
    (net (code "50") (name "unconnected-(U1-PA4-Pad5)") (class "Default")
      (node (ref "U1") (pin "5") (pinfunction "PA4_5") (pintype "passive"))
    )
    (net (code "51") (name "unconnected-(U1-PA7-Pad8)") (class "Default")
      (node (ref "U1") (pin "8") (pinfunction "PA7_8") (pintype "passive"))
    )
    (net (code "52") (name "unconnected-(U1-PB0-Pad14)") (class "Default")
      (node (ref "U1") (pin "14") (pinfunction "PB0_14") (pintype "passive"))
    )
    (net (code "53") (name "unconnected-(U1-PB1-Pad13)") (class "Default")
      (node (ref "U1") (pin "13") (pinfunction "PB1_13") (pintype "passive"))
    )
    (net (code "54") (name "unconnected-(U1-PB2-Pad12)") (class "Default")
      (node (ref "U1") (pin "12") (pinfunction "PB2_12") (pintype "passive"))
    )
    (net (code "55") (name "unconnected-(U1-PB3-Pad11)") (class "Default")
      (node (ref "U1") (pin "11") (pinfunction "PB3_11") (pintype "passive"))
    )
    (net (code "56") (name "unconnected-(U1-PB5-Pad9)") (class "Default")
      (node (ref "U1") (pin "9") (pinfunction "PB5_9") (pintype "passive"))
    )
    (net (code "57") (name "unconnected-(U1-PC0-Pad15)") (class "Default")
      (node (ref "U1") (pin "15") (pinfunction "PC0_15") (pintype "passive"))
    )
    (net (code "58") (name "unconnected-(U1-PC1-Pad16)") (class "Default")
      (node (ref "U1") (pin "16") (pinfunction "PC1_16") (pintype "passive"))
    )
    (net (code "59") (name "unconnected-(U1-PC3-Pad18)") (class "Default")
      (node (ref "U1") (pin "18") (pinfunction "PC3_18") (pintype "passive"))
    )
  )
)
